# msp432mini_rev1_3.net
KiCad netlist of a schematic drawn in EAGLE
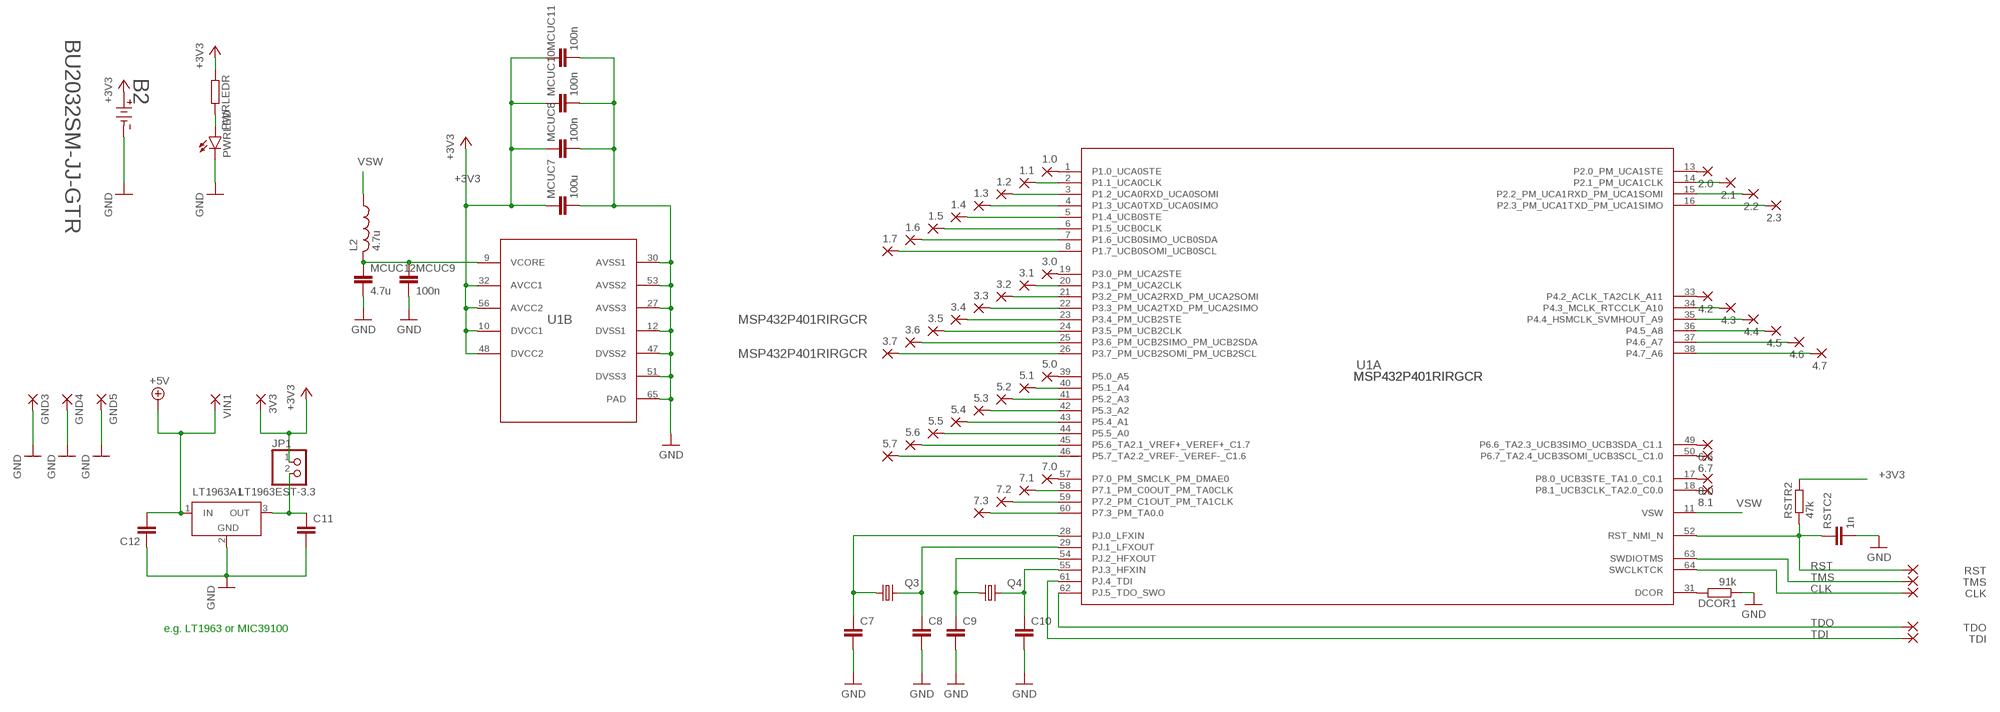
[diagram p0: schematic, sheet 1]

(export (version "E")
  (design (tool "Eeschema 10.0.6"))
  (components
    (comp (ref "1.0")
      (value "1,6/0,9")
      (footprint "eagle-import:1,6_0,9")
      (libsource (lib "eagle-import") (part "1,6/0,9"))
    )
    (comp (ref "1.1")
      (value "1,6/0,9")
      (footprint "eagle-import:1,6_0,9")
      (libsource (lib "eagle-import") (part "1,6/0,9"))
    )
    (comp (ref "1.2")
      (value "1,6/0,9")
      (footprint "eagle-import:1,6_0,9")
      (libsource (lib "eagle-import") (part "1,6/0,9"))
    )
    (comp (ref "1.3")
      (value "1,6/0,9")
      (footprint "eagle-import:1,6_0,9")
      (libsource (lib "eagle-import") (part "1,6/0,9"))
    )
    (comp (ref "1.4")
      (value "1,6/0,9")
      (footprint "eagle-import:1,6_0,9")
      (libsource (lib "eagle-import") (part "1,6/0,9"))
    )
    (comp (ref "1.5")
      (value "1,6/0,9")
      (footprint "eagle-import:1,6_0,9")
      (libsource (lib "eagle-import") (part "1,6/0,9"))
    )
    (comp (ref "1.6")
      (value "1,6/0,9")
      (footprint "eagle-import:1,6_0,9")
      (libsource (lib "eagle-import") (part "1,6/0,9"))
    )
    (comp (ref "1.7")
      (value "1,6/0,9")
      (footprint "eagle-import:1,6_0,9")
      (libsource (lib "eagle-import") (part "1,6/0,9"))
    )
    (comp (ref "2.0")
      (value "1,6/0,9")
      (footprint "eagle-import:1,6_0,9")
      (libsource (lib "eagle-import") (part "1,6/0,9"))
    )
    (comp (ref "2.1")
      (value "1,6/0,9")
      (footprint "eagle-import:1,6_0,9")
      (libsource (lib "eagle-import") (part "1,6/0,9"))
    )
    (comp (ref "2.2")
      (value "1,6/0,9")
      (footprint "eagle-import:1,6_0,9")
      (libsource (lib "eagle-import") (part "1,6/0,9"))
    )
    (comp (ref "2.3")
      (value "1,6/0,9")
      (footprint "eagle-import:1,6_0,9")
      (libsource (lib "eagle-import") (part "1,6/0,9"))
    )
    (comp (ref "3.0")
      (value "1,6/0,9")
      (footprint "eagle-import:1,6_0,9")
      (libsource (lib "eagle-import") (part "1,6/0,9"))
    )
    (comp (ref "3.1")
      (value "1,6/0,9")
      (footprint "eagle-import:1,6_0,9")
      (libsource (lib "eagle-import") (part "1,6/0,9"))
    )
    (comp (ref "3.2")
      (value "1,6/0,9")
      (footprint "eagle-import:1,6_0,9")
      (libsource (lib "eagle-import") (part "1,6/0,9"))
    )
    (comp (ref "3.3")
      (value "1,6/0,9")
      (footprint "eagle-import:1,6_0,9")
      (libsource (lib "eagle-import") (part "1,6/0,9"))
    )
    (comp (ref "3.4")
      (value "1,6/0,9")
      (footprint "eagle-import:1,6_0,9")
      (libsource (lib "eagle-import") (part "1,6/0,9"))
    )
    (comp (ref "3.5")
      (value "1,6/0,9")
      (footprint "eagle-import:1,6_0,9")
      (libsource (lib "eagle-import") (part "1,6/0,9"))
    )
    (comp (ref "3.6")
      (value "1,6/0,9")
      (footprint "eagle-import:1,6_0,9")
      (libsource (lib "eagle-import") (part "1,6/0,9"))
    )
    (comp (ref "3.7")
      (value "1,6/0,9")
      (footprint "eagle-import:1,6_0,9")
      (libsource (lib "eagle-import") (part "1,6/0,9"))
    )
    (comp (ref "3V3")
      (value "1,6/0,9")
      (footprint "eagle-import:1,6_0,9")
      (libsource (lib "eagle-import") (part "1,6/0,9"))
    )
    (comp (ref "4.2")
      (value "1,6/0,9")
      (footprint "eagle-import:1,6_0,9")
      (libsource (lib "eagle-import") (part "1,6/0,9"))
    )
    (comp (ref "4.3")
      (value "1,6/0,9")
      (footprint "eagle-import:1,6_0,9")
      (libsource (lib "eagle-import") (part "1,6/0,9"))
    )
    (comp (ref "4.4")
      (value "1,6/0,9")
      (footprint "eagle-import:1,6_0,9")
      (libsource (lib "eagle-import") (part "1,6/0,9"))
    )
    (comp (ref "4.5")
      (value "1,6/0,9")
      (footprint "eagle-import:1,6_0,9")
      (libsource (lib "eagle-import") (part "1,6/0,9"))
    )
    (comp (ref "4.6")
      (value "1,6/0,9")
      (footprint "eagle-import:1,6_0,9")
      (libsource (lib "eagle-import") (part "1,6/0,9"))
    )
    (comp (ref "4.7")
      (value "1,6/0,9")
      (footprint "eagle-import:1,6_0,9")
      (libsource (lib "eagle-import") (part "1,6/0,9"))
    )
    (comp (ref "5.0")
      (value "1,6/0,9")
      (footprint "eagle-import:1,6_0,9")
      (libsource (lib "eagle-import") (part "1,6/0,9"))
    )
    (comp (ref "5.1")
      (value "1,6/0,9")
      (footprint "eagle-import:1,6_0,9")
      (libsource (lib "eagle-import") (part "1,6/0,9"))
    )
    (comp (ref "5.2")
      (value "1,6/0,9")
      (footprint "eagle-import:1,6_0,9")
      (libsource (lib "eagle-import") (part "1,6/0,9"))
    )
    (comp (ref "5.3")
      (value "1,6/0,9")
      (footprint "eagle-import:1,6_0,9")
      (libsource (lib "eagle-import") (part "1,6/0,9"))
    )
    (comp (ref "5.4")
      (value "1,6/0,9")
      (footprint "eagle-import:1,6_0,9")
      (libsource (lib "eagle-import") (part "1,6/0,9"))
    )
    (comp (ref "5.5")
      (value "1,6/0,9")
      (footprint "eagle-import:1,6_0,9")
      (libsource (lib "eagle-import") (part "1,6/0,9"))
    )
    (comp (ref "5.6")
      (value "1,6/0,9")
      (footprint "eagle-import:1,6_0,9")
      (libsource (lib "eagle-import") (part "1,6/0,9"))
    )
    (comp (ref "5.7")
      (value "1,6/0,9")
      (footprint "eagle-import:1,6_0,9")
      (libsource (lib "eagle-import") (part "1,6/0,9"))
    )
    (comp (ref "6.6")
      (value "1,6/0,9")
      (footprint "eagle-import:1,6_0,9")
      (libsource (lib "eagle-import") (part "1,6/0,9"))
    )
    (comp (ref "6.7")
      (value "1,6/0,9")
      (footprint "eagle-import:1,6_0,9")
      (libsource (lib "eagle-import") (part "1,6/0,9"))
    )
    (comp (ref "7.0")
      (value "1,6/0,9")
      (footprint "eagle-import:1,6_0,9")
      (libsource (lib "eagle-import") (part "1,6/0,9"))
    )
    (comp (ref "7.1")
      (value "1,6/0,9")
      (footprint "eagle-import:1,6_0,9")
      (libsource (lib "eagle-import") (part "1,6/0,9"))
    )
    (comp (ref "7.2")
      (value "1,6/0,9")
      (footprint "eagle-import:1,6_0,9")
      (libsource (lib "eagle-import") (part "1,6/0,9"))
    )
    (comp (ref "7.3")
      (value "1,6/0,9")
      (footprint "eagle-import:1,6_0,9")
      (libsource (lib "eagle-import") (part "1,6/0,9"))
    )
    (comp (ref "8.0")
      (value "1,6/0,9")
      (footprint "eagle-import:1,6_0,9")
      (libsource (lib "eagle-import") (part "1,6/0,9"))
    )
    (comp (ref "8.1")
      (value "1,6/0,9")
      (footprint "eagle-import:1,6_0,9")
      (libsource (lib "eagle-import") (part "1,6/0,9"))
    )
    (comp (ref "B2")
      (value "BU2032SM-JJ-GTR")
      (footprint "eagle-import:BU2032SM-JJ-GTR_MPD")
      (fields (field (name "COPYRIGHT") "Copyright (C) 2018 Accelerated Designs. All rights reserved"))
      (libsource (lib "eagle-import") (part "BU2032SM-JJ-GTR"))
    )
    (comp (ref "C7")
      (value "C-EUC0402K")
      (footprint "eagle-import:C0402K")
      (libsource (lib "eagle-import") (part "C-EUC0402K"))
    )
    (comp (ref "C8")
      (value "C-EUC0402K")
      (footprint "eagle-import:C0402K")
      (libsource (lib "eagle-import") (part "C-EUC0402K"))
    )
    (comp (ref "C9")
      (value "C-EUC0402K")
      (footprint "eagle-import:C0402K")
      (libsource (lib "eagle-import") (part "C-EUC0402K"))
    )
    (comp (ref "C10")
      (value "C-EUC0402K")
      (footprint "eagle-import:C0402K")
      (libsource (lib "eagle-import") (part "C-EUC0402K"))
    )
    (comp (ref "C11")
      (value "C-EUC1206K")
      (footprint "eagle-import:C1206K")
      (libsource (lib "eagle-import") (part "C-EUC1206K"))
    )
    (comp (ref "C12")
      (value "C-EUC1206K")
      (footprint "eagle-import:C1206K")
      (libsource (lib "eagle-import") (part "C-EUC1206K"))
    )
    (comp (ref "CLK")
      (value "1,6/0,9")
      (footprint "eagle-import:1,6_0,9")
      (libsource (lib "eagle-import") (part "1,6/0,9"))
    )
    (comp (ref "DCOR1")
      (value "91k")
      (footprint "eagle-import:R0603")
      (libsource (lib "eagle-import") (part "R-EU_R0603"))
    )
    (comp (ref "GND3")
      (value "1,6/0,9")
      (footprint "eagle-import:1,6_0,9")
      (libsource (lib "eagle-import") (part "1,6/0,9"))
    )
    (comp (ref "GND4")
      (value "1,6/0,9")
      (footprint "eagle-import:1,6_0,9")
      (libsource (lib "eagle-import") (part "1,6/0,9"))
    )
    (comp (ref "GND5")
      (value "1,6/0,9")
      (footprint "eagle-import:1,6_0,9")
      (libsource (lib "eagle-import") (part "1,6/0,9"))
    )
    (comp (ref "JP1")
      (value "PINHD-1X2")
      (footprint "eagle-import:1X02")
      (libsource (lib "eagle-import") (part "PINHD-1X2"))
    )
    (comp (ref "L2")
      (value "4.7u")
      (footprint "eagle-import:L2012C")
      (libsource (lib "eagle-import") (part "L-USL2012C"))
    )
    (comp (ref "LT1963A1")
      (value "LT1963EST-3.3")
      (footprint "eagle-import:SOT223")
      (libsource (lib "eagle-import") (part "LT1963EST-3.3"))
    )
    (comp (ref "MCUC7")
      (value "100u")
      (footprint "eagle-import:C1206K")
      (libsource (lib "eagle-import") (part "resistor_348_C-EUC1206K"))
    )
    (comp (ref "MCUC8")
      (value "100n")
      (footprint "eagle-import:C0603K")
      (libsource (lib "eagle-import") (part "resistor_348_C-EUC0603K"))
    )
    (comp (ref "MCUC9")
      (value "100n")
      (footprint "eagle-import:C0603K")
      (libsource (lib "eagle-import") (part "resistor_348_C-EUC0603K"))
    )
    (comp (ref "MCUC10")
      (value "100n")
      (footprint "eagle-import:C0603K")
      (libsource (lib "eagle-import") (part "resistor_348_C-EUC0603K"))
    )
    (comp (ref "MCUC11")
      (value "100n")
      (footprint "eagle-import:C0603K")
      (libsource (lib "eagle-import") (part "resistor_348_C-EUC0603K"))
    )
    (comp (ref "MCUC12")
      (value "4.7u")
      (footprint "eagle-import:C0603K")
      (libsource (lib "eagle-import") (part "resistor_348_C-EUC0603K"))
    )
    (comp (ref "PWRLED")
      (value "LEDCHIP-LED0805")
      (footprint "eagle-import:CHIP-LED0805")
      (libsource (lib "eagle-import") (part "LEDCHIP-LED0805"))
    )
    (comp (ref "PWRLEDR")
      (value "R-EU_R0603")
      (footprint "eagle-import:R0603")
      (libsource (lib "eagle-import") (part "R-EU_R0603"))
    )
    (comp (ref "Q3")
      (value "KX-327-NHF")
      (footprint "eagle-import:3.2X1.5")
      (libsource (lib "eagle-import") (part "KX-327-NHF"))
    )
    (comp (ref "Q4")
      (value "KX-7")
      (footprint "eagle-import:3.2X2.5_KX-7")
      (libsource (lib "eagle-import") (part "KX-7"))
    )
    (comp (ref "RST")
      (value "1,6/0,9")
      (footprint "eagle-import:1,6_0,9")
      (libsource (lib "eagle-import") (part "1,6/0,9"))
    )
    (comp (ref "RSTC2")
      (value "1n")
      (footprint "eagle-import:C0603K")
      (libsource (lib "eagle-import") (part "C-EUC0603K"))
    )
    (comp (ref "RSTR2")
      (value "47k")
      (footprint "eagle-import:R0603")
      (libsource (lib "eagle-import") (part "R-EU_R0603"))
    )
    (comp (ref "TDI")
      (value "1,6/0,9")
      (footprint "eagle-import:1,6_0,9")
      (libsource (lib "eagle-import") (part "1,6/0,9"))
    )
    (comp (ref "TDO")
      (value "1,6/0,9")
      (footprint "eagle-import:1,6_0,9")
      (libsource (lib "eagle-import") (part "1,6/0,9"))
    )
    (comp (ref "TMS")
      (value "1,6/0,9")
      (footprint "eagle-import:1,6_0,9")
      (libsource (lib "eagle-import") (part "1,6/0,9"))
    )
    (comp (ref "U1")
      (value "MSP432P401RIRGCR")
      (footprint "eagle-import:RGC0064B")
      (libsource (lib "eagle-import") (part "MSP432P401RIRGCR"))
    )
    (comp (ref "VIN1")
      (value "1,6/0,9")
      (footprint "eagle-import:1,6_0,9")
      (libsource (lib "eagle-import") (part "1,6/0,9"))
    )
  )
  (nets
    (net (code "1") (name "+3V3") (class "Default")
      (node (ref "3V3") (pin "1") (pinfunction "P_1") (pintype "passive"))
      (node (ref "B2") (pin "2") (pinfunction "2_2") (pintype "passive"))
      (node (ref "JP1") (pin "1") (pinfunction "1_1") (pintype "passive"))
      (node (ref "MCUC10") (pin "1") (pinfunction "1_1") (pintype "passive"))
      (node (ref "MCUC11") (pin "1") (pinfunction "1_1") (pintype "passive"))
      (node (ref "MCUC7") (pin "1") (pinfunction "1_1") (pintype "passive"))
      (node (ref "MCUC8") (pin "1") (pinfunction "1_1") (pintype "passive"))
      (node (ref "PWRLEDR") (pin "1") (pinfunction "1_1") (pintype "passive"))
      (node (ref "RSTR2") (pin "2") (pinfunction "2_2") (pintype "passive"))
      (node (ref "U1") (pin "10") (pinfunction "DVCC1_10") (pintype "power_in"))
      (node (ref "U1") (pin "32") (pinfunction "AVCC1_32") (pintype "power_in"))
      (node (ref "U1") (pin "48") (pinfunction "DVCC2_48") (pintype "power_in"))
      (node (ref "U1") (pin "56") (pinfunction "AVCC2_56") (pintype "power_in"))
    )
    (net (code "2") (name "+5V") (class "Default")
      (node (ref "C12") (pin "2") (pinfunction "2_2") (pintype "passive"))
      (node (ref "LT1963A1") (pin "1") (pinfunction "IN_1") (pintype "input"))
      (node (ref "VIN1") (pin "1") (pinfunction "P_1") (pintype "passive"))
    )
    (net (code "3") (name "/CLK") (class "Default")
      (node (ref "CLK") (pin "1") (pinfunction "P_1") (pintype "passive"))
      (node (ref "U1") (pin "64") (pinfunction "SWCLKTCK_64") (pintype "input"))
    )
    (net (code "4") (name "/RST") (class "Default")
      (node (ref "RST") (pin "1") (pinfunction "P_1") (pintype "passive"))
      (node (ref "RSTC2") (pin "1") (pinfunction "1_1") (pintype "passive"))
      (node (ref "RSTR2") (pin "1") (pinfunction "1_1") (pintype "passive"))
      (node (ref "U1") (pin "52") (pinfunction "RST_NMI_N_52") (pintype "input"))
    )
    (net (code "5") (name "/TDI") (class "Default")
      (node (ref "TDI") (pin "1") (pinfunction "P_1") (pintype "passive"))
      (node (ref "U1") (pin "61") (pinfunction "PJ.4_TDI_61") (pintype "bidirectional"))
    )
    (net (code "6") (name "/TDO") (class "Default")
      (node (ref "TDO") (pin "1") (pinfunction "P_1") (pintype "passive"))
      (node (ref "U1") (pin "62") (pinfunction "PJ.5_TDO_SWO_62") (pintype "bidirectional"))
    )
    (net (code "7") (name "/TMS") (class "Default")
      (node (ref "TMS") (pin "1") (pinfunction "P_1") (pintype "passive"))
      (node (ref "U1") (pin "63") (pinfunction "SWDIOTMS_63") (pintype "bidirectional"))
    )
    (net (code "8") (name "/VSW") (class "Default")
      (node (ref "L2") (pin "1") (pinfunction "1_1") (pintype "passive"))
      (node (ref "U1") (pin "11") (pinfunction "VSW_11") (pintype "power_in"))
    )
    (net (code "9") (name "GND") (class "Default")
      (node (ref "B2") (pin "1") (pinfunction "1_1") (pintype "passive"))
      (node (ref "C10") (pin "2") (pinfunction "2_2") (pintype "passive"))
      (node (ref "C11") (pin "2") (pinfunction "2_2") (pintype "passive"))
      (node (ref "C12") (pin "1") (pinfunction "1_1") (pintype "passive"))
      (node (ref "C7") (pin "2") (pinfunction "2_2") (pintype "passive"))
      (node (ref "C8") (pin "2") (pinfunction "2_2") (pintype "passive"))
      (node (ref "C9") (pin "2") (pinfunction "2_2") (pintype "passive"))
      (node (ref "DCOR1") (pin "1") (pinfunction "1_1") (pintype "passive"))
      (node (ref "GND3") (pin "1") (pinfunction "P_1") (pintype "passive"))
      (node (ref "GND4") (pin "1") (pinfunction "P_1") (pintype "passive"))
      (node (ref "GND5") (pin "1") (pinfunction "P_1") (pintype "passive"))
      (node (ref "LT1963A1") (pin "2") (pinfunction "GND_2") (pintype "power_in"))
      (node (ref "MCUC10") (pin "2") (pinfunction "2_2") (pintype "passive"))
      (node (ref "MCUC11") (pin "2") (pinfunction "2_2") (pintype "passive"))
      (node (ref "MCUC12") (pin "2") (pinfunction "2_2") (pintype "passive"))
      (node (ref "MCUC7") (pin "2") (pinfunction "2_2") (pintype "passive"))
      (node (ref "MCUC8") (pin "2") (pinfunction "2_2") (pintype "passive"))
      (node (ref "MCUC9") (pin "2") (pinfunction "2_2") (pintype "passive"))
      (node (ref "PWRLED") (pin "C") (pinfunction "C_C") (pintype "passive"))
      (node (ref "RSTC2") (pin "2") (pinfunction "2_2") (pintype "passive"))
      (node (ref "U1") (pin "12") (pinfunction "DVSS1_12") (pintype "power_in"))
      (node (ref "U1") (pin "27") (pinfunction "AVSS3_27") (pintype "power_in"))
      (node (ref "U1") (pin "30") (pinfunction "AVSS1_30") (pintype "power_in"))
      (node (ref "U1") (pin "47") (pinfunction "DVSS2_47") (pintype "power_in"))
      (node (ref "U1") (pin "51") (pinfunction "DVSS3_51") (pintype "power_in"))
      (node (ref "U1") (pin "53") (pinfunction "AVSS2_53") (pintype "power_in"))
      (node (ref "U1") (pin "65") (pinfunction "PAD_65") (pintype "passive"))
    )
    (net (code "10") (name "Net-(1.0-P)") (class "Default")
      (node (ref "1.0") (pin "1") (pinfunction "P_1") (pintype "passive"))
      (node (ref "U1") (pin "1") (pinfunction "P1.0_UCA0STE_1") (pintype "bidirectional"))
    )
    (net (code "11") (name "Net-(1.1-P)") (class "Default")
      (node (ref "1.1") (pin "1") (pinfunction "P_1") (pintype "passive"))
      (node (ref "U1") (pin "2") (pinfunction "P1.1_UCA0CLK_2") (pintype "bidirectional"))
    )
    (net (code "12") (name "Net-(1.2-P)") (class "Default")
      (node (ref "1.2") (pin "1") (pinfunction "P_1") (pintype "passive"))
      (node (ref "U1") (pin "3") (pinfunction "P1.2_UCA0RXD_UCA0SOMI_3") (pintype "bidirectional"))
    )
    (net (code "13") (name "Net-(1.3-P)") (class "Default")
      (node (ref "1.3") (pin "1") (pinfunction "P_1") (pintype "passive"))
      (node (ref "U1") (pin "4") (pinfunction "P1.3_UCA0TXD_UCA0SIMO_4") (pintype "bidirectional"))
    )
    (net (code "14") (name "Net-(1.4-P)") (class "Default")
      (node (ref "1.4") (pin "1") (pinfunction "P_1") (pintype "passive"))
      (node (ref "U1") (pin "5") (pinfunction "P1.4_UCB0STE_5") (pintype "bidirectional"))
    )
    (net (code "15") (name "Net-(1.5-P)") (class "Default")
      (node (ref "1.5") (pin "1") (pinfunction "P_1") (pintype "passive"))
      (node (ref "U1") (pin "6") (pinfunction "P1.5_UCB0CLK_6") (pintype "bidirectional"))
    )
    (net (code "16") (name "Net-(1.6-P)") (class "Default")
      (node (ref "1.6") (pin "1") (pinfunction "P_1") (pintype "passive"))
      (node (ref "U1") (pin "7") (pinfunction "P1.6_UCB0SIMO_UCB0SDA_7") (pintype "bidirectional"))
    )
    (net (code "17") (name "Net-(1.7-P)") (class "Default")
      (node (ref "1.7") (pin "1") (pinfunction "P_1") (pintype "passive"))
      (node (ref "U1") (pin "8") (pinfunction "P1.7_UCB0SOMI_UCB0SCL_8") (pintype "bidirectional"))
    )
    (net (code "18") (name "Net-(2.0-P)") (class "Default")
      (node (ref "2.0") (pin "1") (pinfunction "P_1") (pintype "passive"))
      (node (ref "U1") (pin "13") (pinfunction "P2.0_PM_UCA1STE_13") (pintype "bidirectional"))
    )
    (net (code "19") (name "Net-(2.1-P)") (class "Default")
      (node (ref "2.1") (pin "1") (pinfunction "P_1") (pintype "passive"))
      (node (ref "U1") (pin "14") (pinfunction "P2.1_PM_UCA1CLK_14") (pintype "bidirectional"))
    )
    (net (code "20") (name "Net-(2.2-P)") (class "Default")
      (node (ref "2.2") (pin "1") (pinfunction "P_1") (pintype "passive"))
      (node (ref "U1") (pin "15") (pinfunction "P2.2_PM_UCA1RXD_PM_UCA1SOMI_15") (pintype "bidirectional"))
    )
    (net (code "21") (name "Net-(2.3-P)") (class "Default")
      (node (ref "2.3") (pin "1") (pinfunction "P_1") (pintype "passive"))
      (node (ref "U1") (pin "16") (pinfunction "P2.3_PM_UCA1TXD_PM_UCA1SIMO_16") (pintype "bidirectional"))
    )
    (net (code "22") (name "Net-(3.0-P)") (class "Default")
      (node (ref "3.0") (pin "1") (pinfunction "P_1") (pintype "passive"))
      (node (ref "U1") (pin "19") (pinfunction "P3.0_PM_UCA2STE_19") (pintype "bidirectional"))
    )
    (net (code "23") (name "Net-(3.1-P)") (class "Default")
      (node (ref "3.1") (pin "1") (pinfunction "P_1") (pintype "passive"))
      (node (ref "U1") (pin "20") (pinfunction "P3.1_PM_UCA2CLK_20") (pintype "bidirectional"))
    )
    (net (code "24") (name "Net-(3.2-P)") (class "Default")
      (node (ref "3.2") (pin "1") (pinfunction "P_1") (pintype "passive"))
      (node (ref "U1") (pin "21") (pinfunction "P3.2_PM_UCA2RXD_PM_UCA2SOMI_21") (pintype "bidirectional"))
    )
    (net (code "25") (name "Net-(3.3-P)") (class "Default")
      (node (ref "3.3") (pin "1") (pinfunction "P_1") (pintype "passive"))
      (node (ref "U1") (pin "22") (pinfunction "P3.3_PM_UCA2TXD_PM_UCA2SIMO_22") (pintype "bidirectional"))
    )
    (net (code "26") (name "Net-(3.4-P)") (class "Default")
      (node (ref "3.4") (pin "1") (pinfunction "P_1") (pintype "passive"))
      (node (ref "U1") (pin "23") (pinfunction "P3.4_PM_UCB2STE_23") (pintype "bidirectional"))
    )
    (net (code "27") (name "Net-(3.5-P)") (class "Default")
      (node (ref "3.5") (pin "1") (pinfunction "P_1") (pintype "passive"))
      (node (ref "U1") (pin "24") (pinfunction "P3.5_PM_UCB2CLK_24") (pintype "bidirectional"))
    )
    (net (code "28") (name "Net-(3.6-P)") (class "Default")
      (node (ref "3.6") (pin "1") (pinfunction "P_1") (pintype "passive"))
      (node (ref "U1") (pin "25") (pinfunction "P3.6_PM_UCB2SIMO_PM_UCB2SDA_25") (pintype "bidirectional"))
    )
    (net (code "29") (name "Net-(3.7-P)") (class "Default")
      (node (ref "3.7") (pin "1") (pinfunction "P_1") (pintype "passive"))
      (node (ref "U1") (pin "26") (pinfunction "P3.7_PM_UCB2SOMI_PM_UCB2SCL_26") (pintype "bidirectional"))
    )
    (net (code "30") (name "Net-(4.2-P)") (class "Default")
      (node (ref "4.2") (pin "1") (pinfunction "P_1") (pintype "passive"))
      (node (ref "U1") (pin "33") (pinfunction "P4.2_ACLK_TA2CLK_A11_33") (pintype "bidirectional"))
    )
    (net (code "31") (name "Net-(4.3-P)") (class "Default")
      (node (ref "4.3") (pin "1") (pinfunction "P_1") (pintype "passive"))
      (node (ref "U1") (pin "34") (pinfunction "P4.3_MCLK_RTCCLK_A10_34") (pintype "bidirectional"))
    )
    (net (code "32") (name "Net-(4.4-P)") (class "Default")
      (node (ref "4.4") (pin "1") (pinfunction "P_1") (pintype "passive"))
      (node (ref "U1") (pin "35") (pinfunction "P4.4_HSMCLK_SVMHOUT_A9_35") (pintype "bidirectional"))
    )
    (net (code "33") (name "Net-(4.5-P)") (class "Default")
      (node (ref "4.5") (pin "1") (pinfunction "P_1") (pintype "passive"))
      (node (ref "U1") (pin "36") (pinfunction "P4.5_A8_36") (pintype "bidirectional"))
    )
    (net (code "34") (name "Net-(4.6-P)") (class "Default")
      (node (ref "4.6") (pin "1") (pinfunction "P_1") (pintype "passive"))
      (node (ref "U1") (pin "37") (pinfunction "P4.6_A7_37") (pintype "bidirectional"))
    )
    (net (code "35") (name "Net-(4.7-P)") (class "Default")
      (node (ref "4.7") (pin "1") (pinfunction "P_1") (pintype "passive"))
      (node (ref "U1") (pin "38") (pinfunction "P4.7_A6_38") (pintype "bidirectional"))
    )
    (net (code "36") (name "Net-(5.0-P)") (class "Default")
      (node (ref "5.0") (pin "1") (pinfunction "P_1") (pintype "passive"))
      (node (ref "U1") (pin "39") (pinfunction "P5.0_A5_39") (pintype "bidirectional"))
    )
    (net (code "37") (name "Net-(5.1-P)") (class "Default")
      (node (ref "5.1") (pin "1") (pinfunction "P_1") (pintype "passive"))
      (node (ref "U1") (pin "40") (pinfunction "P5.1_A4_40") (pintype "bidirectional"))
    )
    (net (code "38") (name "Net-(5.2-P)") (class "Default")
      (node (ref "5.2") (pin "1") (pinfunction "P_1") (pintype "passive"))
      (node (ref "U1") (pin "41") (pinfunction "P5.2_A3_41") (pintype "bidirectional"))
    )
    (net (code "39") (name "Net-(5.3-P)") (class "Default")
      (node (ref "5.3") (pin "1") (pinfunction "P_1") (pintype "passive"))
      (node (ref "U1") (pin "42") (pinfunction "P5.3_A2_42") (pintype "bidirectional"))
    )
    (net (code "40") (name "Net-(5.4-P)") (class "Default")
      (node (ref "5.4") (pin "1") (pinfunction "P_1") (pintype "passive"))
      (node (ref "U1") (pin "43") (pinfunction "P5.4_A1_43") (pintype "bidirectional"))
    )
    (net (code "41") (name "Net-(5.5-P)") (class "Default")
      (node (ref "5.5") (pin "1") (pinfunction "P_1") (pintype "passive"))
      (node (ref "U1") (pin "44") (pinfunction "P5.5_A0_44") (pintype "bidirectional"))
    )
    (net (code "42") (name "Net-(5.6-P)") (class "Default")
      (node (ref "5.6") (pin "1") (pinfunction "P_1") (pintype "passive"))
      (node (ref "U1") (pin "45") (pinfunction "P5.6_TA2.1_VREF+_VEREF+_C1.7_45") (pintype "bidirectional"))
    )
    (net (code "43") (name "Net-(5.7-P)") (class "Default")
      (node (ref "5.7") (pin "1") (pinfunction "P_1") (pintype "passive"))
      (node (ref "U1") (pin "46") (pinfunction "P5.7_TA2.2_VREF-_VEREF-_C1.6_46") (pintype "bidirectional"))
    )
    (net (code "44") (name "Net-(6.6-P)") (class "Default")
      (node (ref "6.6") (pin "1") (pinfunction "P_1") (pintype "passive"))
      (node (ref "U1") (pin "49") (pinfunction "P6.6_TA2.3_UCB3SIMO_UCB3SDA_C1.1_49") (pintype "bidirectional"))
    )
    (net (code "45") (name "Net-(6.7-P)") (class "Default")
      (node (ref "6.7") (pin "1") (pinfunction "P_1") (pintype "passive"))
      (node (ref "U1") (pin "50") (pinfunction "P6.7_TA2.4_UCB3SOMI_UCB3SCL_C1.0_50") (pintype "bidirectional"))
    )
    (net (code "46") (name "Net-(7.0-P)") (class "Default")
      (node (ref "7.0") (pin "1") (pinfunction "P_1") (pintype "passive"))
      (node (ref "U1") (pin "57") (pinfunction "P7.0_PM_SMCLK_PM_DMAE0_57") (pintype "bidirectional"))
    )
    (net (code "47") (name "Net-(7.1-P)") (class "Default")
      (node (ref "7.1") (pin "1") (pinfunction "P_1") (pintype "passive"))
      (node (ref "U1") (pin "58") (pinfunction "P7.1_PM_C0OUT_PM_TA0CLK_58") (pintype "bidirectional"))
    )
    (net (code "48") (name "Net-(7.2-P)") (class "Default")
      (node (ref "7.2") (pin "1") (pinfunction "P_1") (pintype "passive"))
      (node (ref "U1") (pin "59") (pinfunction "P7.2_PM_C1OUT_PM_TA1CLK_59") (pintype "bidirectional"))
    )
    (net (code "49") (name "Net-(7.3-P)") (class "Default")
      (node (ref "7.3") (pin "1") (pinfunction "P_1") (pintype "passive"))
      (node (ref "U1") (pin "60") (pinfunction "P7.3_PM_TA0.0_60") (pintype "bidirectional"))
    )
    (net (code "50") (name "Net-(8.0-P)") (class "Default")
      (node (ref "8.0") (pin "1") (pinfunction "P_1") (pintype "passive"))
      (node (ref "U1") (pin "17") (pinfunction "P8.0_UCB3STE_TA1.0_C0.1_17") (pintype "bidirectional"))
    )
    (net (code "51") (name "Net-(8.1-P)") (class "Default")
      (node (ref "8.1") (pin "1") (pinfunction "P_1") (pintype "passive"))
      (node (ref "U1") (pin "18") (pinfunction "P8.1_UCB3CLK_TA2.0_C0.0_18") (pintype "bidirectional"))
    )
    (net (code "52") (name "Net-(LT1963A1A-OUT)") (class "Default")
      (node (ref "C11") (pin "1") (pinfunction "1_1") (pintype "passive"))
      (node (ref "JP1") (pin "2") (pinfunction "2_2") (pintype "passive"))
      (node (ref "LT1963A1") (pin "3") (pinfunction "OUT_3") (pintype "output"))
    )
    (net (code "53") (name "Net-(PWRLED-PadA)") (class "Default")
      (node (ref "PWRLED") (pin "A") (pinfunction "A_A") (pintype "passive"))
      (node (ref "PWRLEDR") (pin "2") (pinfunction "2_2") (pintype "passive"))
    )
    (net (code "54") (name "Net-(Q4-2)") (class "Default")
      (node (ref "C10") (pin "1") (pinfunction "1_1") (pintype "passive"))
      (node (ref "Q4") (pin "3") (pinfunction "2_3") (pintype "passive"))
      (node (ref "U1") (pin "55") (pinfunction "PJ.3_HFXIN_55") (pintype "bidirectional"))
    )
    (net (code "55") (name "Net-(U1A-DCOR)") (class "Default")
      (node (ref "DCOR1") (pin "2") (pinfunction "2_2") (pintype "passive"))
      (node (ref "U1") (pin "31") (pinfunction "DCOR_31") (pintype "passive"))
    )
    (net (code "56") (name "Net-(U1A-PJ.0_LFXIN)") (class "Default")
      (node (ref "C7") (pin "1") (pinfunction "1_1") (pintype "passive"))
      (node (ref "Q3") (pin "1") (pinfunction "1_1") (pintype "passive"))
      (node (ref "U1") (pin "28") (pinfunction "PJ.0_LFXIN_28") (pintype "bidirectional"))
    )
    (net (code "57") (name "Net-(U1A-PJ.1_LFXOUT)") (class "Default")
      (node (ref "C8") (pin "1") (pinfunction "1_1") (pintype "passive"))
      (node (ref "Q3") (pin "2") (pinfunction "2_2") (pintype "passive"))
      (node (ref "U1") (pin "29") (pinfunction "PJ.1_LFXOUT_29") (pintype "bidirectional"))
    )
    (net (code "58") (name "Net-(U1A-PJ.2_HFXOUT)") (class "Default")
      (node (ref "C9") (pin "1") (pinfunction "1_1") (pintype "passive"))
      (node (ref "Q4") (pin "1") (pinfunction "1_1") (pintype "passive"))
      (node (ref "U1") (pin "54") (pinfunction "PJ.2_HFXOUT_54") (pintype "bidirectional"))
    )
    (net (code "59") (name "Net-(U1B-VCORE)") (class "Default")
      (node (ref "L2") (pin "2") (pinfunction "2_2") (pintype "passive"))
      (node (ref "MCUC12") (pin "1") (pinfunction "1_1") (pintype "passive"))
      (node (ref "MCUC9") (pin "1") (pinfunction "1_1") (pintype "passive"))
      (node (ref "U1") (pin "9") (pinfunction "VCORE_9") (pintype "power_in"))
    )
  )
)
